# Audio.net
KiCad netlist of a schematic drawn in Altium Designer
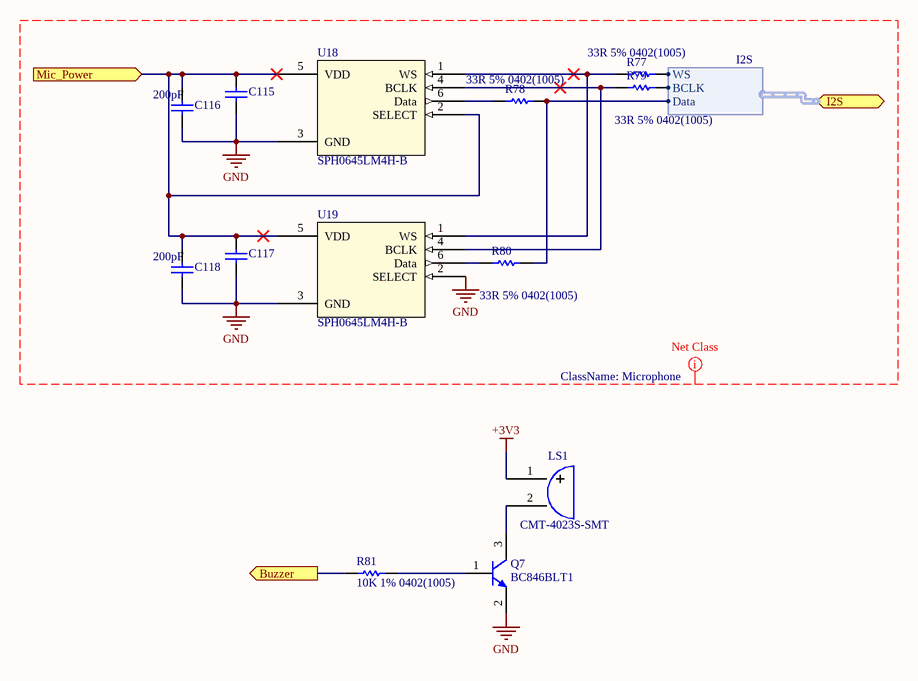
[diagram p0: Audio.SchDoc]

(export (version "E")
  (design (tool "Eeschema 10.0.6"))
  (components
    (comp (ref "C115")
      (value "CAP 100nF 10V 0402(1005)")
      (footprint "CAPC0402(1005)60_L")
      (description "CAP 100nF 10V ±20% 0402 (1005 Metric) Thickness 0.6mm SMD")
      (fields (field (name "TOLERANCE") "Â±20%"))
      (libsource (lib "Altium Content Vault") (part "CAP"))
    )
    (comp (ref "C116")
      (value "200pF")
      (footprint "CAPC0402(1005)60_L")
      (description "CAP 200pF 10V ±1% 0402 (1005 Metric) Thickness 0.6mm SMD")
      (fields (field (name "TOLERANCE") "Â±1%") (field (name "Comment") "CAP 200pF 10V 0402(1005)"))
      (libsource (lib "Altium Content Vault") (part "CMP-1034-01342-1"))
    )
    (comp (ref "C117")
      (value "CAP 100nF 10V 0402(1005)")
      (footprint "CAPC0402(1005)60_L")
      (description "CAP 100nF 10V ±20% 0402 (1005 Metric) Thickness 0.6mm SMD")
      (fields (field (name "TOLERANCE") "Â±20%"))
      (libsource (lib "Altium Content Vault") (part "CAP"))
    )
    (comp (ref "C118")
      (value "200pF")
      (footprint "CAPC0402(1005)60_L")
      (description "CAP 200pF 10V ±1% 0402 (1005 Metric) Thickness 0.6mm SMD")
      (fields (field (name "TOLERANCE") "Â±1%") (field (name "Comment") "CAP 200pF 10V 0402(1005)"))
      (libsource (lib "Altium Content Vault") (part "CMP-1034-01342-1"))
    )
    (comp (ref "LS1")
      (value "CMT-4023S-SMT")
      (footprint "CMT-4023S-SMT")
      (description "Buzzer")
      (libsource (lib "CMT-4023S-SMT") (part "CMT-4023S-SMT"))
    )
    (comp (ref "Q7")
      (value "BC846BLT1")
      (footprint "ONSC-SOT-23-3-318-08_V")
      (description "General Purpose Transistor, NPN Silicon, 3-Pin SOT-23, Tape and Reel")
      (fields (field (name "MANUFACTURER") "On Semiconductor"))
      (libsource (lib "Altium Content Vault") (part "ONSC-NPN-B1E2C3-3"))
    )
    (comp (ref "R77")
      (value "33R 5% 0402(1005)")
      (footprint "RESC0402(1005)_M")
      (description "33R 0.063W 5% 0402 (1005 Metric)  SMD")
      (fields (field (name "TOLERANCE") "5 %") (field (name "POWER") "0.063 W"))
      (libsource (lib "Altium Content Vault") (part "RES"))
    )
    (comp (ref "R78")
      (value "33R 5% 0402(1005)")
      (footprint "RESC0402(1005)_M")
      (description "33R 0.063W 5% 0402 (1005 Metric)  SMD")
      (fields (field (name "TOLERANCE") "5 %") (field (name "POWER") "0.063 W"))
      (libsource (lib "Altium Content Vault") (part "RES"))
    )
    (comp (ref "R79")
      (value "33R 5% 0402(1005)")
      (footprint "RESC0402(1005)_M")
      (description "33R 0.063W 5% 0402 (1005 Metric)  SMD")
      (fields (field (name "TOLERANCE") "5 %") (field (name "POWER") "0.063 W"))
      (libsource (lib "Altium Content Vault") (part "RES"))
    )
    (comp (ref "R80")
      (value "33R 5% 0402(1005)")
      (footprint "RESC0402(1005)_M")
      (description "33R 0.063W 5% 0402 (1005 Metric)  SMD")
      (fields (field (name "TOLERANCE") "5 %") (field (name "POWER") "0.063 W"))
      (libsource (lib "Altium Content Vault") (part "RES"))
    )
    (comp (ref "R81")
      (value "10K 1% 0402(1005)")
      (footprint "RESC0402(1005)_L")
      (description "10K 0.063W 1% 0402 (1005 Metric)  SMD")
      (fields (field (name "TOLERANCE") "1 %") (field (name "POWER") "0.063 W"))
      (libsource (lib "Altium Content Vault") (part "RES"))
    )
    (comp (ref "U18")
      (value "SPH0645LM4H-B")
      (footprint "SPH0645LM4H-B")
      (libsource (lib "SPH0645LM4H-B") (part "SPH0645LM4H-B"))
    )
    (comp (ref "U19")
      (value "SPH0645LM4H-B")
      (footprint "SPH0645LM4H-B")
      (libsource (lib "SPH0645LM4H-B") (part "SPH0645LM4H-B"))
    )
  )
  (nets
    (net (code "2") (name "+3V3") (class "Default")
      (node (ref "LS1") (pin "1") (pinfunction "+_1") (pintype "power_in"))
    )
    (net (code "3") (name "/BCLK") (class "Default")
      (node (ref "R79") (pin "2") (pinfunction "2_2") (pintype "passive"))
    )
    (net (code "4") (name "/Buzzer") (class "Default")
      (node (ref "R81") (pin "1") (pinfunction "1_1") (pintype "passive"))
    )
    (net (code "5") (name "/Data") (class "Default")
      (node (ref "R78") (pin "2") (pinfunction "2_2") (pintype "passive"))
      (node (ref "R80") (pin "2") (pinfunction "2_2") (pintype "passive"))
    )
    (net (code "6") (name "/Mic_Power") (class "Default")
      (node (ref "C115") (pin "2") (pinfunction "2_2") (pintype "passive"))
      (node (ref "C116") (pin "2") (pinfunction "2_2") (pintype "passive"))
      (node (ref "C117") (pin "2") (pinfunction "2_2") (pintype "passive"))
      (node (ref "C118") (pin "2") (pinfunction "2_2") (pintype "passive"))
      (node (ref "U18") (pin "2") (pinfunction "SELECT_2") (pintype "input"))
      (node (ref "U18") (pin "5") (pinfunction "VDD_5") (pintype "power_in"))
      (node (ref "U19") (pin "5") (pinfunction "VDD_5") (pintype "power_in"))
    )
    (net (code "7") (name "/WS") (class "Default")
      (node (ref "R77") (pin "2") (pinfunction "2_2") (pintype "passive"))
    )
    (net (code "9") (name "GND") (class "Default")
      (node (ref "C115") (pin "1") (pinfunction "1_1") (pintype "passive"))
      (node (ref "C116") (pin "1") (pinfunction "1_1") (pintype "passive"))
      (node (ref "C117") (pin "1") (pinfunction "1_1") (pintype "passive"))
      (node (ref "C118") (pin "1") (pinfunction "1_1") (pintype "passive"))
      (node (ref "Q7") (pin "2") (pinfunction "E_2") (pintype "passive"))
      (node (ref "U18") (pin "3") (pinfunction "GND_3") (pintype "power_in"))
      (node (ref "U19") (pin "2") (pinfunction "SELECT_2") (pintype "input"))
      (node (ref "U19") (pin "3") (pinfunction "GND_3") (pintype "power_in"))
    )
    (net (code "10") (name "Net-(LS1--)") (class "Default")
      (node (ref "LS1") (pin "2") (pinfunction "-_2") (pintype "power_in"))
      (node (ref "Q7") (pin "3") (pinfunction "C_3") (pintype "passive"))
    )
    (net (code "11") (name "Net-(Q7-B)") (class "Default")
      (node (ref "Q7") (pin "1") (pinfunction "B_1") (pintype "passive"))
      (node (ref "R81") (pin "2") (pinfunction "2_2") (pintype "passive"))
    )
    (net (code "12") (name "Net-(U18-BCLK)") (class "Default")
      (node (ref "R79") (pin "1") (pinfunction "1_1") (pintype "passive"))
      (node (ref "U18") (pin "4") (pinfunction "BCLK_4") (pintype "input"))
      (node (ref "U19") (pin "4") (pinfunction "BCLK_4") (pintype "input"))
    )
    (net (code "13") (name "Net-(U18-Data)") (class "Default")
      (node (ref "R78") (pin "1") (pinfunction "1_1") (pintype "passive"))
      (node (ref "U18") (pin "6") (pinfunction "Data_6") (pintype "output"))
    )
    (net (code "14") (name "Net-(U18-WS)") (class "Default")
      (node (ref "R77") (pin "1") (pinfunction "1_1") (pintype "passive"))
      (node (ref "U18") (pin "1") (pinfunction "WS_1") (pintype "input"))
      (node (ref "U19") (pin "1") (pinfunction "WS_1") (pintype "input"))
    )
    (net (code "15") (name "Net-(U19-Data)") (class "Default")
      (node (ref "R80") (pin "1") (pinfunction "1_1") (pintype "passive"))
      (node (ref "U19") (pin "6") (pinfunction "Data_6") (pintype "output"))
    )
  )
)
